# Flowmeter_Ansteuerung.net
KiCad netlist of a schematic drawn in EAGLE
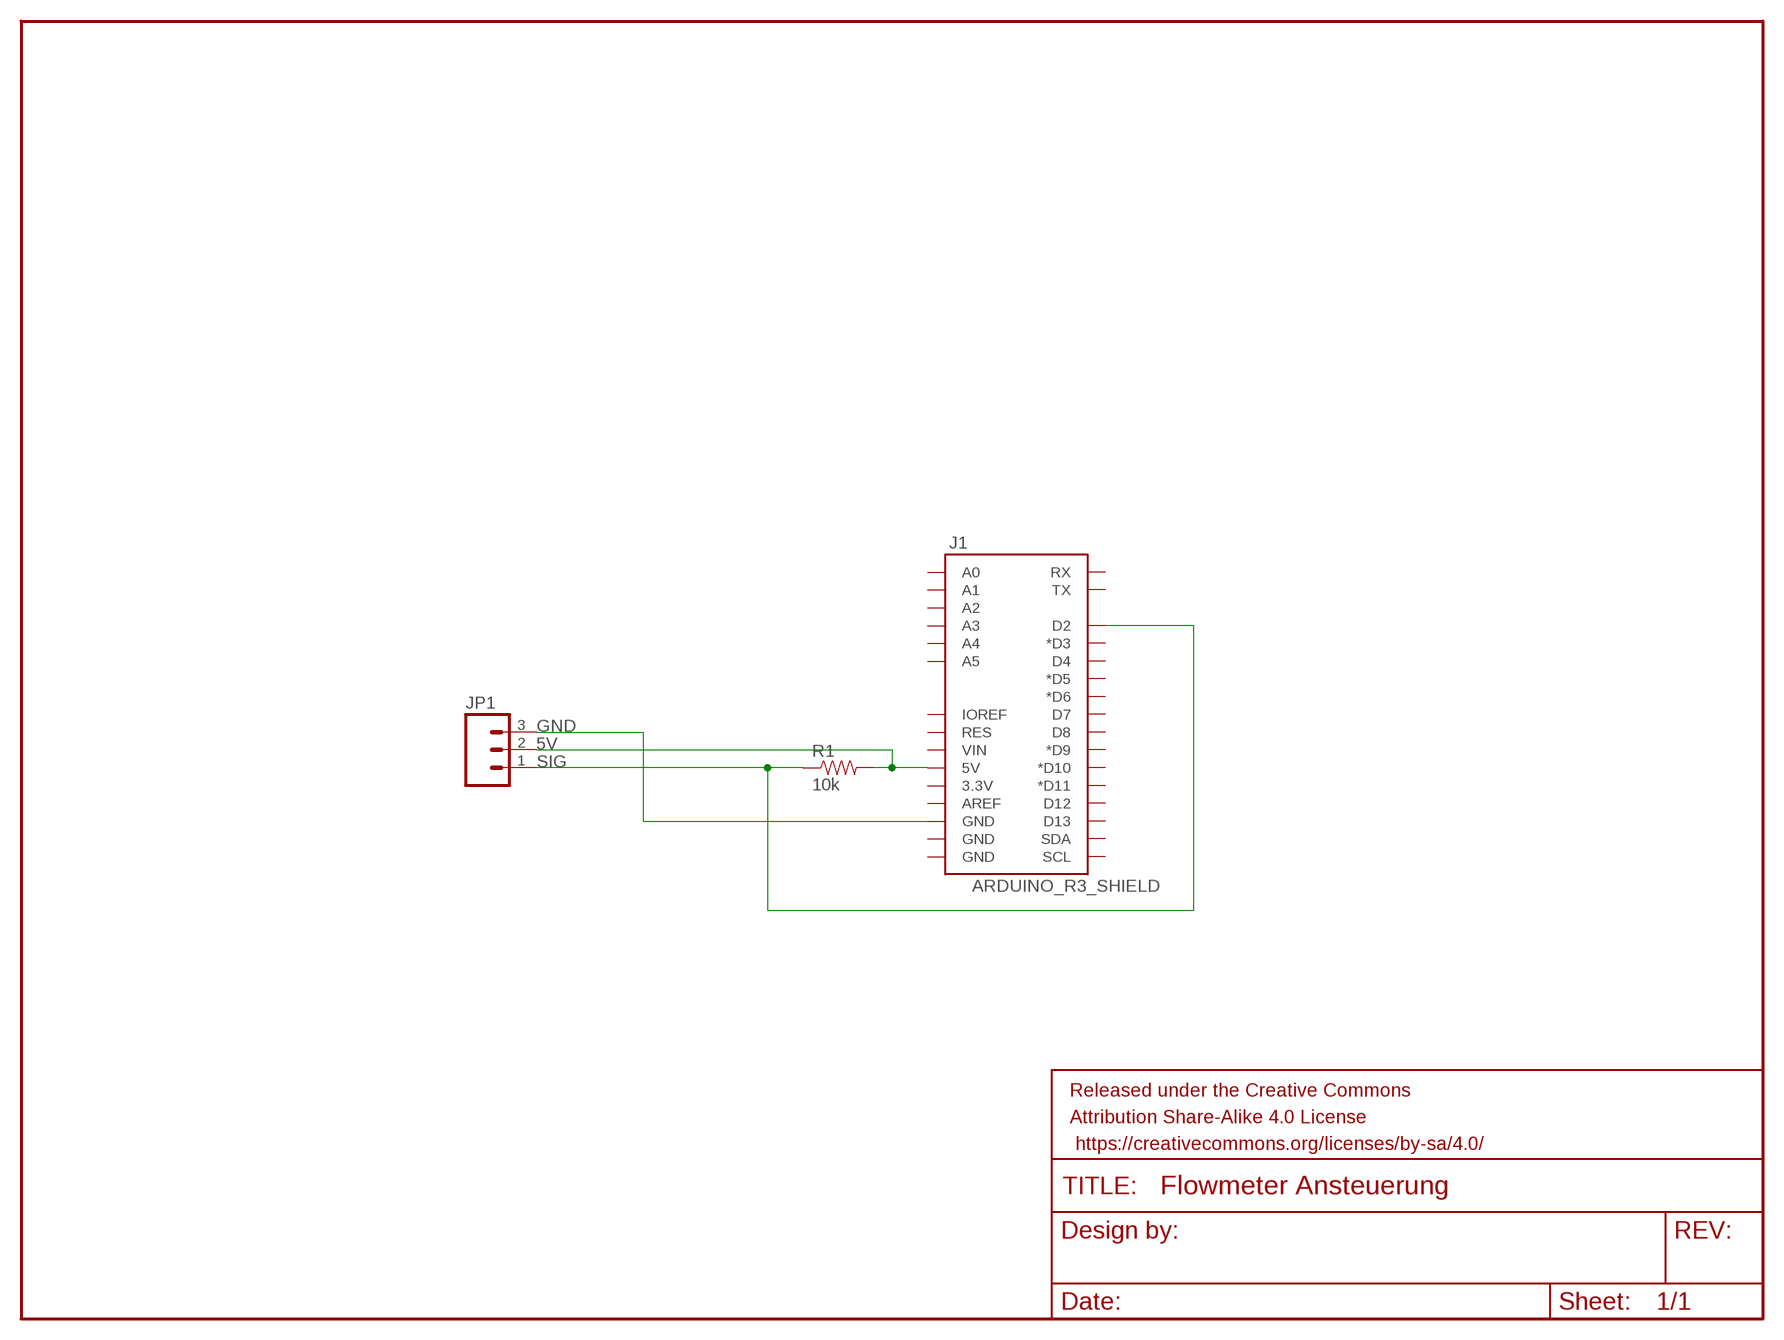
[diagram p0: schematic, sheet 1]

(export (version "E")
  (design (tool "Eeschema 10.0.6"))
  (components
    (comp (ref "FRAME1")
      (value "FRAME-LETTER")
      (footprint "eagle-import:CREATIVE_COMMONS")
      (fields (field (name "DESIGNER") "NAME"))
      (libsource (lib "eagle-import") (part "FRAME-LETTER"))
    )
    (comp (ref "J1")
      (value "ARDUINO_R3_SHIELD")
      (footprint "eagle-import:UNO_R3_SHIELD")
      (libsource (lib "eagle-import") (part "ARDUINO_R3_SHIELD"))
    )
    (comp (ref "JP1")
      (value "M03LOCK")
      (footprint "eagle-import:1X03_LOCK")
      (libsource (lib "eagle-import") (part "M03LOCK"))
    )
    (comp (ref "R1")
      (value "10k")
      (footprint "eagle-import:AXIAL-0.3")
      (libsource (lib "eagle-import") (part "10KOHM-1/4W-1%(PTH)HORIZ"))
    )
  )
  (nets
    (net (code "1") (name "/5V") (class "Default")
      (node (ref "J1") (pin "5V") (pinfunction "5V_5V") (pintype "bidirectional"))
      (node (ref "JP1") (pin "2") (pinfunction "2_2") (pintype "passive"))
      (node (ref "R1") (pin "P$2") (pinfunction "2_P$2") (pintype "passive"))
    )
    (net (code "2") (name "/GND") (class "Default")
      (node (ref "J1") (pin "GND@2") (pinfunction "GND_GND@2") (pintype "bidirectional"))
      (node (ref "JP1") (pin "3") (pinfunction "3_3") (pintype "passive"))
    )
    (net (code "3") (name "/SIG") (class "Default")
      (node (ref "J1") (pin "D2") (pinfunction "D2_D2") (pintype "bidirectional"))
      (node (ref "JP1") (pin "1") (pinfunction "1_1") (pintype "passive"))
      (node (ref "R1") (pin "P$1") (pinfunction "1_P$1") (pintype "passive"))
    )
    (net (code "4") (name "unconnected-(J1-*D3-PadD3)") (class "Default")
      (node (ref "J1") (pin "D3") (pinfunction "*D3_D3") (pintype "bidirectional"))
    )
    (net (code "5") (name "unconnected-(J1-*D5-PadD5)") (class "Default")
      (node (ref "J1") (pin "D5") (pinfunction "*D5_D5") (pintype "bidirectional"))
    )
    (net (code "6") (name "unconnected-(J1-*D6-PadD6)") (class "Default")
      (node (ref "J1") (pin "D6") (pinfunction "*D6_D6") (pintype "bidirectional"))
    )
    (net (code "7") (name "unconnected-(J1-*D9-PadD9)") (class "Default")
      (node (ref "J1") (pin "D9") (pinfunction "*D9_D9") (pintype "bidirectional"))
    )
    (net (code "8") (name "unconnected-(J1-*D10-PadD10)") (class "Default")
      (node (ref "J1") (pin "D10") (pinfunction "*D10_D10") (pintype "bidirectional"))
    )
    (net (code "9") (name "unconnected-(J1-*D11-PadD11)") (class "Default")
      (node (ref "J1") (pin "D11") (pinfunction "*D11_D11") (pintype "bidirectional"))
    )
    (net (code "10") (name "unconnected-(J1-GND-PadGND@0)") (class "Default")
      (node (ref "J1") (pin "GND@0") (pinfunction "GND_GND@0") (pintype "bidirectional"))
    )
    (net (code "11") (name "unconnected-(J1-GND-PadGND@1)") (class "Default")
      (node (ref "J1") (pin "GND@1") (pinfunction "GND_GND@1") (pintype "bidirectional"))
    )
    (net (code "12") (name "unconnected-(J1-Pad3.3V)") (class "Default")
      (node (ref "J1") (pin "3.3V") (pinfunction "3.3V_3.3V") (pintype "bidirectional"))
    )
    (net (code "13") (name "unconnected-(J1-PadA0)") (class "Default")
      (node (ref "J1") (pin "A0") (pinfunction "A0_A0") (pintype "bidirectional"))
    )
    (net (code "14") (name "unconnected-(J1-PadA1)") (class "Default")
      (node (ref "J1") (pin "A1") (pinfunction "A1_A1") (pintype "bidirectional"))
    )
    (net (code "15") (name "unconnected-(J1-PadA2)") (class "Default")
      (node (ref "J1") (pin "A2") (pinfunction "A2_A2") (pintype "bidirectional"))
    )
    (net (code "16") (name "unconnected-(J1-PadA3)") (class "Default")
      (node (ref "J1") (pin "A3") (pinfunction "A3_A3") (pintype "bidirectional"))
    )
    (net (code "17") (name "unconnected-(J1-PadA4)") (class "Default")
      (node (ref "J1") (pin "A4") (pinfunction "A4_A4") (pintype "bidirectional"))
    )
    (net (code "18") (name "unconnected-(J1-PadA5)") (class "Default")
      (node (ref "J1") (pin "A5") (pinfunction "A5_A5") (pintype "bidirectional"))
    )
    (net (code "19") (name "unconnected-(J1-PadAREF)") (class "Default")
      (node (ref "J1") (pin "AREF") (pinfunction "AREF_AREF") (pintype "bidirectional"))
    )
    (net (code "20") (name "unconnected-(J1-PadD4)") (class "Default")
      (node (ref "J1") (pin "D4") (pinfunction "D4_D4") (pintype "bidirectional"))
    )
    (net (code "21") (name "unconnected-(J1-PadD7)") (class "Default")
      (node (ref "J1") (pin "D7") (pinfunction "D7_D7") (pintype "bidirectional"))
    )
    (net (code "22") (name "unconnected-(J1-PadD8)") (class "Default")
      (node (ref "J1") (pin "D8") (pinfunction "D8_D8") (pintype "bidirectional"))
    )
    (net (code "23") (name "unconnected-(J1-PadD12)") (class "Default")
      (node (ref "J1") (pin "D12") (pinfunction "D12_D12") (pintype "bidirectional"))
    )
    (net (code "24") (name "unconnected-(J1-PadD13)") (class "Default")
      (node (ref "J1") (pin "D13") (pinfunction "D13_D13") (pintype "bidirectional"))
    )
    (net (code "25") (name "unconnected-(J1-PadIOREF)") (class "Default")
      (node (ref "J1") (pin "IOREF") (pinfunction "IOREF_IOREF") (pintype "bidirectional"))
    )
    (net (code "26") (name "unconnected-(J1-PadRES)") (class "Default")
      (node (ref "J1") (pin "RES") (pinfunction "RES_RES") (pintype "bidirectional"))
    )
    (net (code "27") (name "unconnected-(J1-PadRX)") (class "Default")
      (node (ref "J1") (pin "RX") (pinfunction "RX_RX") (pintype "bidirectional"))
    )
    (net (code "28") (name "unconnected-(J1-PadSCL)") (class "Default")
      (node (ref "J1") (pin "SCL") (pinfunction "SCL_SCL") (pintype "bidirectional"))
    )
    (net (code "29") (name "unconnected-(J1-PadSDA)") (class "Default")
      (node (ref "J1") (pin "SDA") (pinfunction "SDA_SDA") (pintype "bidirectional"))
    )
    (net (code "30") (name "unconnected-(J1-PadTX)") (class "Default")
      (node (ref "J1") (pin "TX") (pinfunction "TX_TX") (pintype "bidirectional"))
    )
    (net (code "31") (name "unconnected-(J1-PadVIN)") (class "Default")
      (node (ref "J1") (pin "VIN") (pinfunction "VIN_VIN") (pintype "bidirectional"))
    )
  )
)
